# US_shield.net
KiCad netlist of a schematic drawn in Altium Designer
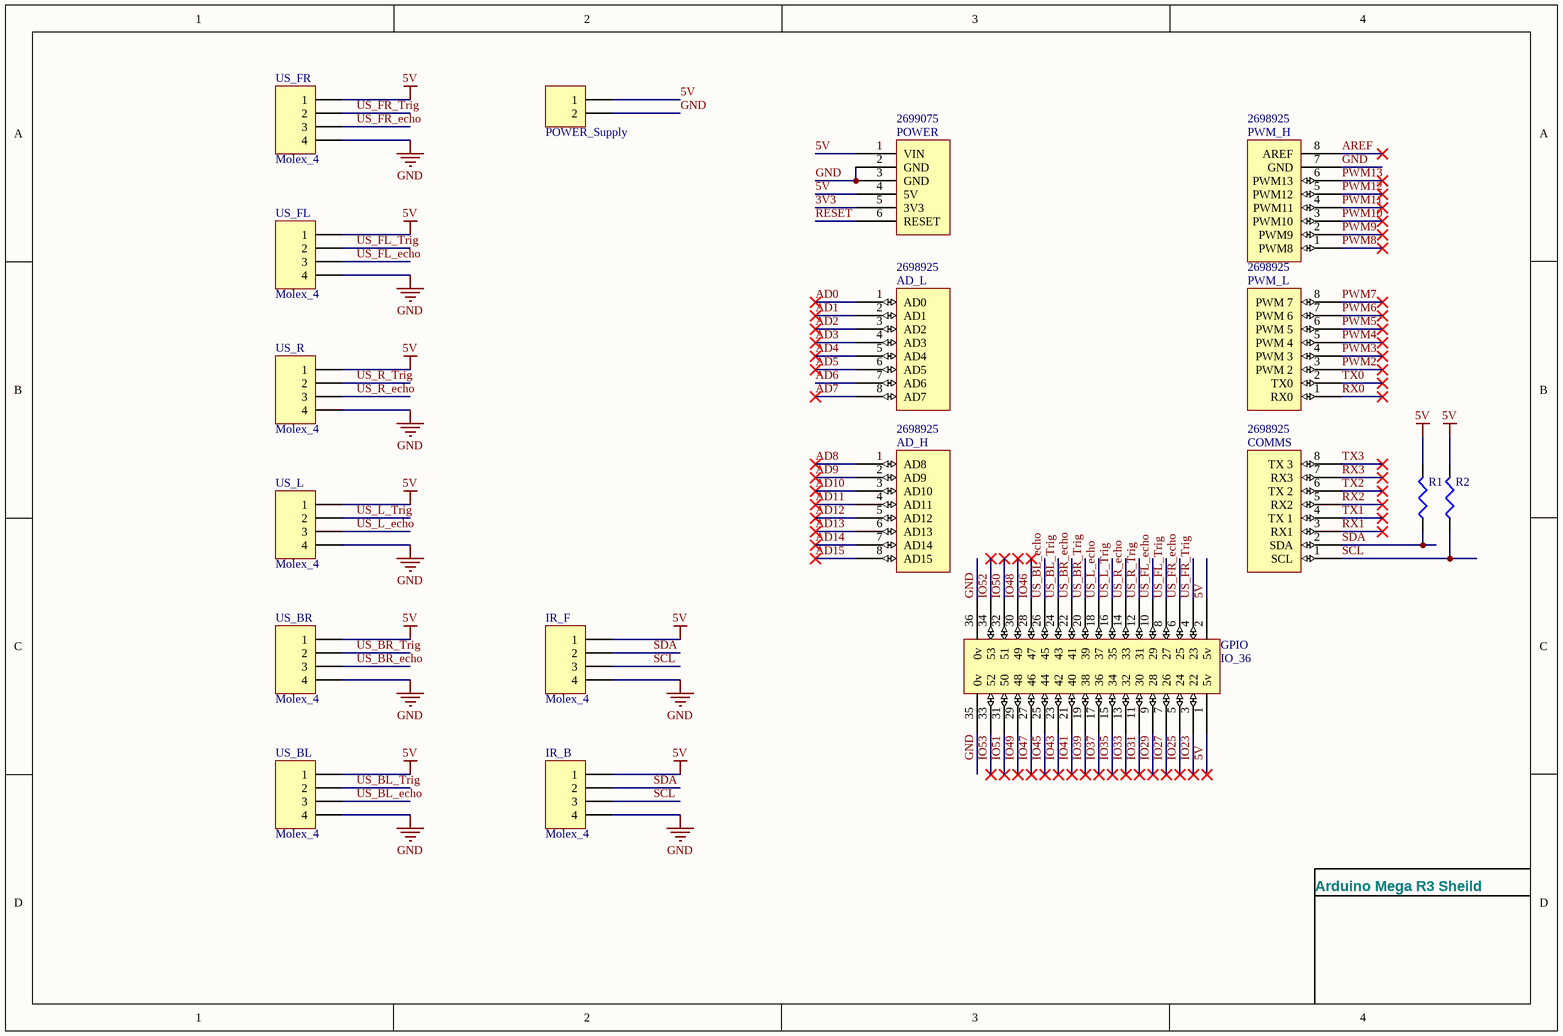
[diagram p0: US_shield.SchDoc]

(export (version "E")
  (design (tool "Eeschema 10.0.6"))
  (components
    (comp (ref "AD_H")
      (value "AD_H")
      (footprint "Header 8x1 8.5mm")
      (fields (field (name "SUPPLIER PART NUMBER 4") "2698925"))
      (libsource (lib "Header") (part "AD_H"))
    )
    (comp (ref "AD_L")
      (value "AD_L")
      (footprint "Header 8x1 8.5mm")
      (fields (field (name "SUPPLIER PART NUMBER 5") "2698925"))
      (libsource (lib "Header") (part "AD_L"))
    )
    (comp (ref "COMMS")
      (value "Communication")
      (footprint "Header 8x1 8.5mm")
      (fields (field (name "SUPPLIER PART NUMBER 4") "2698925"))
      (libsource (lib "Header") (part "Communication"))
    )
    (comp (ref "GPIO")
      (value "IO_36")
      (footprint "HEADER 36X 8MM")
      (description "Header, 36-Pin")
      (libsource (lib "HBLib") (part "IO_36"))
    )
    (comp (ref "IR_B")
      (value "Molex_4")
      (footprint "Header4_ecam")
      (description "Header, 4-Pin")
      (fields (field (name "PUBLISHER") "Altium Limited"))
      (libsource (lib "Pump_lib") (part "Molex_4"))
    )
    (comp (ref "IR_F")
      (value "Molex_4")
      (footprint "Header4_ecam")
      (description "Header, 4-Pin")
      (fields (field (name "PUBLISHER") "Altium Limited"))
      (libsource (lib "Pump_lib") (part "Molex_4"))
    )
    (comp (ref "POWER")
      (value "POWER")
      (footprint "Header 6x1 8.5mm")
      (fields (field (name "SUPPLIER PART NUMBER 2") "2699075"))
      (libsource (lib "Header") (part "POWER"))
    )
    (comp (ref "POWER_Supply")
      (value "Molex_2")
      (footprint "Header_2Ecam")
      (description "Header, 2-pin")
      (fields (field (name "DESIGNER") "ECAM 2005"))
      (libsource (lib "Pump_lib") (part "Molex_2"))
    )
    (comp (ref "PWM_H")
      (value "PWM_H")
      (footprint "Header 8x1 8.5mm")
      (fields (field (name "SUPPLIER PART NUMBER 4") "2698925"))
      (libsource (lib "Header") (part "PWM_H"))
    )
    (comp (ref "PWM_L")
      (value "PWM_L")
      (footprint "Header 8x1 8.5mm")
      (fields (field (name "SUPPLIER PART NUMBER 4") "2698925"))
      (libsource (lib "Header") (part "PWM_L"))
    )
    (comp (ref "R1")
      (value "Résistance")
      (footprint "AXIAL-0.4")
      (description "Résistance standard")
      (fields (field (name "DESIGNER") "ECAM 2005"))
      (libsource (lib "Pump_lib") (part "Résistance"))
    )
    (comp (ref "R2")
      (value "Résistance")
      (footprint "AXIAL-0.4")
      (description "Résistance standard")
      (fields (field (name "DESIGNER") "ECAM 2005"))
      (libsource (lib "Pump_lib") (part "Résistance"))
    )
    (comp (ref "US_BL")
      (value "Molex_4")
      (footprint "Header4_ecam")
      (description "Header, 4-Pin")
      (fields (field (name "PUBLISHER") "Altium Limited"))
      (libsource (lib "Pump_lib") (part "Molex_4"))
    )
    (comp (ref "US_BR")
      (value "Molex_4")
      (footprint "Header4_ecam")
      (description "Header, 4-Pin")
      (fields (field (name "PUBLISHER") "Altium Limited"))
      (libsource (lib "Pump_lib") (part "Molex_4"))
    )
    (comp (ref "US_FL")
      (value "Molex_4")
      (footprint "Header4_ecam")
      (description "Header, 4-Pin")
      (fields (field (name "PUBLISHER") "Altium Limited"))
      (libsource (lib "Pump_lib") (part "Molex_4"))
    )
    (comp (ref "US_FR")
      (value "Molex_4")
      (footprint "Header4_ecam")
      (description "Header, 4-Pin")
      (fields (field (name "PUBLISHER") "Altium Limited"))
      (libsource (lib "Pump_lib") (part "Molex_4"))
    )
    (comp (ref "US_L")
      (value "Molex_4")
      (footprint "Header4_ecam")
      (description "Header, 4-Pin")
      (fields (field (name "PUBLISHER") "Altium Limited"))
      (libsource (lib "Pump_lib") (part "Molex_4"))
    )
    (comp (ref "US_R")
      (value "Molex_4")
      (footprint "Header4_ecam")
      (description "Header, 4-Pin")
      (fields (field (name "PUBLISHER") "Altium Limited"))
      (libsource (lib "Pump_lib") (part "Molex_4"))
    )
  )
  (nets
    (net (code "1") (name "/3V3") (class "Default")
      (node (ref "POWER") (pin "5") (pinfunction "3V3_5") (pintype "power_in"))
    )
    (net (code "2") (name "/AD0") (class "Default")
      (node (ref "AD_L") (pin "1") (pinfunction "AD0_1") (pintype "bidirectional+no_connect"))
    )
    (net (code "3") (name "/AD1") (class "Default")
      (node (ref "AD_L") (pin "2") (pinfunction "AD1_2") (pintype "bidirectional+no_connect"))
    )
    (net (code "4") (name "/AD2") (class "Default")
      (node (ref "AD_L") (pin "3") (pinfunction "AD2_3") (pintype "bidirectional+no_connect"))
    )
    (net (code "5") (name "/AD3") (class "Default")
      (node (ref "AD_L") (pin "4") (pinfunction "AD3_4") (pintype "bidirectional+no_connect"))
    )
    (net (code "6") (name "/AD4") (class "Default")
      (node (ref "AD_L") (pin "5") (pinfunction "AD4_5") (pintype "bidirectional+no_connect"))
    )
    (net (code "7") (name "/AD5") (class "Default")
      (node (ref "AD_L") (pin "6") (pinfunction "AD5_6") (pintype "bidirectional+no_connect"))
    )
    (net (code "8") (name "/AD6") (class "Default")
      (node (ref "AD_L") (pin "7") (pinfunction "AD6_7") (pintype "bidirectional"))
    )
    (net (code "9") (name "/AD7") (class "Default")
      (node (ref "AD_L") (pin "8") (pinfunction "AD7_8") (pintype "bidirectional+no_connect"))
    )
    (net (code "10") (name "/AD8") (class "Default")
      (node (ref "AD_H") (pin "1") (pinfunction "AD8_1") (pintype "bidirectional+no_connect"))
    )
    (net (code "11") (name "/AD9") (class "Default")
      (node (ref "AD_H") (pin "2") (pinfunction "AD9_2") (pintype "bidirectional+no_connect"))
    )
    (net (code "12") (name "/AD10") (class "Default")
      (node (ref "AD_H") (pin "3") (pinfunction "AD10_3") (pintype "bidirectional+no_connect"))
    )
    (net (code "13") (name "/AD11") (class "Default")
      (node (ref "AD_H") (pin "4") (pinfunction "AD11_4") (pintype "bidirectional+no_connect"))
    )
    (net (code "14") (name "/AD12") (class "Default")
      (node (ref "AD_H") (pin "5") (pinfunction "AD12_5") (pintype "bidirectional+no_connect"))
    )
    (net (code "15") (name "/AD13") (class "Default")
      (node (ref "AD_H") (pin "6") (pinfunction "AD13_6") (pintype "bidirectional+no_connect"))
    )
    (net (code "16") (name "/AD14") (class "Default")
      (node (ref "AD_H") (pin "7") (pinfunction "AD14_7") (pintype "bidirectional+no_connect"))
    )
    (net (code "17") (name "/AD15") (class "Default")
      (node (ref "AD_H") (pin "8") (pinfunction "AD15_8") (pintype "bidirectional+no_connect"))
    )
    (net (code "18") (name "/AREF") (class "Default")
      (node (ref "PWM_H") (pin "8") (pinfunction "AREF_8") (pintype "passive+no_connect"))
    )
    (net (code "19") (name "/IO23") (class "Default")
      (node (ref "GPIO") (pin "3") (pinfunction "22_3") (pintype "bidirectional+no_connect"))
    )
    (net (code "20") (name "/IO25") (class "Default")
      (node (ref "GPIO") (pin "5") (pinfunction "24_5") (pintype "bidirectional+no_connect"))
    )
    (net (code "21") (name "/IO27") (class "Default")
      (node (ref "GPIO") (pin "7") (pinfunction "26_7") (pintype "bidirectional+no_connect"))
    )
    (net (code "22") (name "/IO29") (class "Default")
      (node (ref "GPIO") (pin "9") (pinfunction "28_9") (pintype "bidirectional+no_connect"))
    )
    (net (code "23") (name "/IO31") (class "Default")
      (node (ref "GPIO") (pin "11") (pinfunction "30_11") (pintype "bidirectional+no_connect"))
    )
    (net (code "24") (name "/IO33") (class "Default")
      (node (ref "GPIO") (pin "13") (pinfunction "32_13") (pintype "bidirectional+no_connect"))
    )
    (net (code "25") (name "/IO35") (class "Default")
      (node (ref "GPIO") (pin "15") (pinfunction "34_15") (pintype "bidirectional+no_connect"))
    )
    (net (code "26") (name "/IO37") (class "Default")
      (node (ref "GPIO") (pin "17") (pinfunction "36_17") (pintype "bidirectional+no_connect"))
    )
    (net (code "27") (name "/IO39") (class "Default")
      (node (ref "GPIO") (pin "19") (pinfunction "38_19") (pintype "bidirectional+no_connect"))
    )
    (net (code "28") (name "/IO41") (class "Default")
      (node (ref "GPIO") (pin "21") (pinfunction "40_21") (pintype "bidirectional+no_connect"))
    )
    (net (code "29") (name "/IO43") (class "Default")
      (node (ref "GPIO") (pin "23") (pinfunction "42_23") (pintype "bidirectional+no_connect"))
    )
    (net (code "30") (name "/IO45") (class "Default")
      (node (ref "GPIO") (pin "25") (pinfunction "44_25") (pintype "bidirectional+no_connect"))
    )
    (net (code "31") (name "/IO46") (class "Default")
      (node (ref "GPIO") (pin "28") (pinfunction "47_28") (pintype "bidirectional+no_connect"))
    )
    (net (code "32") (name "/IO47") (class "Default")
      (node (ref "GPIO") (pin "27") (pinfunction "46_27") (pintype "bidirectional+no_connect"))
    )
    (net (code "33") (name "/IO48") (class "Default")
      (node (ref "GPIO") (pin "30") (pinfunction "49_30") (pintype "bidirectional+no_connect"))
    )
    (net (code "34") (name "/IO49") (class "Default")
      (node (ref "GPIO") (pin "29") (pinfunction "48_29") (pintype "bidirectional+no_connect"))
    )
    (net (code "35") (name "/IO50") (class "Default")
      (node (ref "GPIO") (pin "32") (pinfunction "51_32") (pintype "bidirectional+no_connect"))
    )
    (net (code "36") (name "/IO51") (class "Default")
      (node (ref "GPIO") (pin "31") (pinfunction "50_31") (pintype "bidirectional+no_connect"))
    )
    (net (code "37") (name "/IO52") (class "Default")
      (node (ref "GPIO") (pin "34") (pinfunction "53_34") (pintype "bidirectional+no_connect"))
    )
    (net (code "38") (name "/IO53") (class "Default")
      (node (ref "GPIO") (pin "33") (pinfunction "52_33") (pintype "bidirectional+no_connect"))
    )
    (net (code "39") (name "/PWM2") (class "Default")
      (node (ref "PWM_L") (pin "3") (pinfunction "PWM_2_3") (pintype "bidirectional+no_connect"))
    )
    (net (code "40") (name "/PWM3") (class "Default")
      (node (ref "PWM_L") (pin "4") (pinfunction "PWM_3_4") (pintype "bidirectional+no_connect"))
    )
    (net (code "41") (name "/PWM4") (class "Default")
      (node (ref "PWM_L") (pin "5") (pinfunction "PWM_4_5") (pintype "bidirectional+no_connect"))
    )
    (net (code "42") (name "/PWM5") (class "Default")
      (node (ref "PWM_L") (pin "6") (pinfunction "PWM_5_6") (pintype "bidirectional+no_connect"))
    )
    (net (code "43") (name "/PWM6") (class "Default")
      (node (ref "PWM_L") (pin "7") (pinfunction "PWM_6_7") (pintype "bidirectional+no_connect"))
    )
    (net (code "44") (name "/PWM7") (class "Default")
      (node (ref "PWM_L") (pin "8") (pinfunction "PWM_7_8") (pintype "bidirectional+no_connect"))
    )
    (net (code "45") (name "/PWM8") (class "Default")
      (node (ref "PWM_H") (pin "1") (pinfunction "PWM8_1") (pintype "bidirectional+no_connect"))
    )
    (net (code "46") (name "/PWM9") (class "Default")
      (node (ref "PWM_H") (pin "2") (pinfunction "PWM9_2") (pintype "bidirectional+no_connect"))
    )
    (net (code "47") (name "/PWM10") (class "Default")
      (node (ref "PWM_H") (pin "3") (pinfunction "PWM10_3") (pintype "bidirectional+no_connect"))
    )
    (net (code "48") (name "/PWM11") (class "Default")
      (node (ref "PWM_H") (pin "4") (pinfunction "PWM11_4") (pintype "bidirectional+no_connect"))
    )
    (net (code "49") (name "/PWM12") (class "Default")
      (node (ref "PWM_H") (pin "5") (pinfunction "PWM12_5") (pintype "bidirectional+no_connect"))
    )
    (net (code "50") (name "/PWM13") (class "Default")
      (node (ref "PWM_H") (pin "6") (pinfunction "PWM13_6") (pintype "bidirectional+no_connect"))
    )
    (net (code "51") (name "/RESET") (class "Default")
      (node (ref "POWER") (pin "6") (pinfunction "RESET_6") (pintype "passive"))
    )
    (net (code "52") (name "/RX0") (class "Default")
      (node (ref "PWM_L") (pin "1") (pinfunction "RX0_1") (pintype "bidirectional+no_connect"))
    )
    (net (code "53") (name "/RX1") (class "Default")
      (node (ref "COMMS") (pin "3") (pinfunction "RX1_3") (pintype "bidirectional+no_connect"))
    )
    (net (code "54") (name "/RX2") (class "Default")
      (node (ref "COMMS") (pin "5") (pinfunction "RX2_5") (pintype "bidirectional+no_connect"))
    )
    (net (code "55") (name "/RX3") (class "Default")
      (node (ref "COMMS") (pin "7") (pinfunction "RX3_7") (pintype "bidirectional+no_connect"))
    )
    (net (code "56") (name "/SCL") (class "Default")
      (node (ref "COMMS") (pin "1") (pinfunction "SCL_1") (pintype "bidirectional"))
      (node (ref "IR_B") (pin "3") (pinfunction "3_3") (pintype "passive"))
      (node (ref "IR_F") (pin "3") (pinfunction "3_3") (pintype "passive"))
      (node (ref "R2") (pin "1") (pinfunction "1_1") (pintype "passive"))
    )
    (net (code "57") (name "/SDA") (class "Default")
      (node (ref "COMMS") (pin "2") (pinfunction "SDA_2") (pintype "bidirectional"))
      (node (ref "IR_B") (pin "2") (pinfunction "2_2") (pintype "passive"))
      (node (ref "IR_F") (pin "2") (pinfunction "2_2") (pintype "passive"))
      (node (ref "R1") (pin "1") (pinfunction "1_1") (pintype "passive"))
    )
    (net (code "58") (name "/TX0") (class "Default")
      (node (ref "PWM_L") (pin "2") (pinfunction "TX0_2") (pintype "bidirectional+no_connect"))
    )
    (net (code "59") (name "/TX1") (class "Default")
      (node (ref "COMMS") (pin "4") (pinfunction "TX_1_4") (pintype "bidirectional+no_connect"))
    )
    (net (code "60") (name "/TX2") (class "Default")
      (node (ref "COMMS") (pin "6") (pinfunction "TX_2_6") (pintype "bidirectional+no_connect"))
    )
    (net (code "61") (name "/TX3") (class "Default")
      (node (ref "COMMS") (pin "8") (pinfunction "TX_3_8") (pintype "bidirectional+no_connect"))
    )
    (net (code "62") (name "/US_BL_Trig") (class "Default")
      (node (ref "GPIO") (pin "24") (pinfunction "43_24") (pintype "bidirectional"))
      (node (ref "US_BL") (pin "2") (pinfunction "2_2") (pintype "passive"))
    )
    (net (code "63") (name "/US_BL_echo") (class "Default")
      (node (ref "GPIO") (pin "26") (pinfunction "45_26") (pintype "bidirectional"))
      (node (ref "US_BL") (pin "3") (pinfunction "3_3") (pintype "passive"))
    )
    (net (code "64") (name "/US_BR_Trig") (class "Default")
      (node (ref "GPIO") (pin "20") (pinfunction "39_20") (pintype "bidirectional"))
      (node (ref "US_BR") (pin "2") (pinfunction "2_2") (pintype "passive"))
    )
    (net (code "65") (name "/US_BR_echo") (class "Default")
      (node (ref "GPIO") (pin "22") (pinfunction "41_22") (pintype "bidirectional"))
      (node (ref "US_BR") (pin "3") (pinfunction "3_3") (pintype "passive"))
    )
    (net (code "66") (name "/US_FL_Trig") (class "Default")
      (node (ref "GPIO") (pin "8") (pinfunction "27_8") (pintype "bidirectional"))
      (node (ref "US_FL") (pin "2") (pinfunction "2_2") (pintype "passive"))
    )
    (net (code "67") (name "/US_FL_echo") (class "Default")
      (node (ref "GPIO") (pin "10") (pinfunction "29_10") (pintype "bidirectional"))
      (node (ref "US_FL") (pin "3") (pinfunction "3_3") (pintype "passive"))
    )
    (net (code "68") (name "/US_FR_Trig") (class "Default")
      (node (ref "GPIO") (pin "4") (pinfunction "23_4") (pintype "bidirectional"))
      (node (ref "US_FR") (pin "2") (pinfunction "2_2") (pintype "passive"))
    )
    (net (code "69") (name "/US_FR_echo") (class "Default")
      (node (ref "GPIO") (pin "6") (pinfunction "25_6") (pintype "bidirectional"))
      (node (ref "US_FR") (pin "3") (pinfunction "3_3") (pintype "passive"))
    )
    (net (code "70") (name "/US_L_Trig") (class "Default")
      (node (ref "GPIO") (pin "16") (pinfunction "35_16") (pintype "bidirectional"))
      (node (ref "US_L") (pin "2") (pinfunction "2_2") (pintype "passive"))
    )
    (net (code "71") (name "/US_L_echo") (class "Default")
      (node (ref "GPIO") (pin "18") (pinfunction "37_18") (pintype "bidirectional"))
      (node (ref "US_L") (pin "3") (pinfunction "3_3") (pintype "passive"))
    )
    (net (code "72") (name "/US_R_Trig") (class "Default")
      (node (ref "GPIO") (pin "12") (pinfunction "31_12") (pintype "bidirectional"))
      (node (ref "US_R") (pin "2") (pinfunction "2_2") (pintype "passive"))
    )
    (net (code "73") (name "/US_R_echo") (class "Default")
      (node (ref "GPIO") (pin "14") (pinfunction "33_14") (pintype "bidirectional"))
      (node (ref "US_R") (pin "3") (pinfunction "3_3") (pintype "passive"))
    )
    (net (code "74") (name "5V") (class "Default")
      (node (ref "GPIO") (pin "1") (pinfunction "5v_1") (pintype "power_in"))
      (node (ref "GPIO") (pin "2") (pinfunction "5v_2") (pintype "power_in"))
      (node (ref "IR_B") (pin "1") (pinfunction "1_1") (pintype "passive"))
      (node (ref "IR_F") (pin "1") (pinfunction "1_1") (pintype "passive"))
      (node (ref "POWER") (pin "1") (pinfunction "VIN_1") (pintype "power_in"))
      (node (ref "POWER") (pin "4") (pinfunction "5V_4") (pintype "power_in"))
      (node (ref "POWER_Supply") (pin "1") (pinfunction "1_1") (pintype "passive"))
      (node (ref "R1") (pin "2") (pinfunction "2_2") (pintype "passive"))
      (node (ref "R2") (pin "2") (pinfunction "2_2") (pintype "passive"))
      (node (ref "US_BL") (pin "1") (pinfunction "1_1") (pintype "passive"))
      (node (ref "US_BR") (pin "1") (pinfunction "1_1") (pintype "passive"))
      (node (ref "US_FL") (pin "1") (pinfunction "1_1") (pintype "passive"))
      (node (ref "US_FR") (pin "1") (pinfunction "1_1") (pintype "passive"))
      (node (ref "US_L") (pin "1") (pinfunction "1_1") (pintype "passive"))
      (node (ref "US_R") (pin "1") (pinfunction "1_1") (pintype "passive"))
    )
    (net (code "75") (name "GND") (class "Default")
      (node (ref "GPIO") (pin "35") (pinfunction "0v_35") (pintype "power_in"))
      (node (ref "GPIO") (pin "36") (pinfunction "0v_36") (pintype "power_in"))
      (node (ref "IR_B") (pin "4") (pinfunction "4_4") (pintype "passive"))
      (node (ref "IR_F") (pin "4") (pinfunction "4_4") (pintype "passive"))
      (node (ref "POWER") (pin "2") (pinfunction "GND_2") (pintype "power_in"))
      (node (ref "POWER") (pin "3") (pinfunction "GND_3") (pintype "power_in"))
      (node (ref "POWER_Supply") (pin "2") (pinfunction "2_2") (pintype "passive"))
      (node (ref "PWM_H") (pin "7") (pinfunction "GND_7") (pintype "power_in"))
      (node (ref "US_BL") (pin "4") (pinfunction "4_4") (pintype "passive"))
      (node (ref "US_BR") (pin "4") (pinfunction "4_4") (pintype "passive"))
      (node (ref "US_FL") (pin "4") (pinfunction "4_4") (pintype "passive"))
      (node (ref "US_FR") (pin "4") (pinfunction "4_4") (pintype "passive"))
      (node (ref "US_L") (pin "4") (pinfunction "4_4") (pintype "passive"))
      (node (ref "US_R") (pin "4") (pinfunction "4_4") (pintype "passive"))
    )
  )
)
